# AC_MOVE-V3_4.net
KiCad netlist of a schematic drawn in Altium Designer
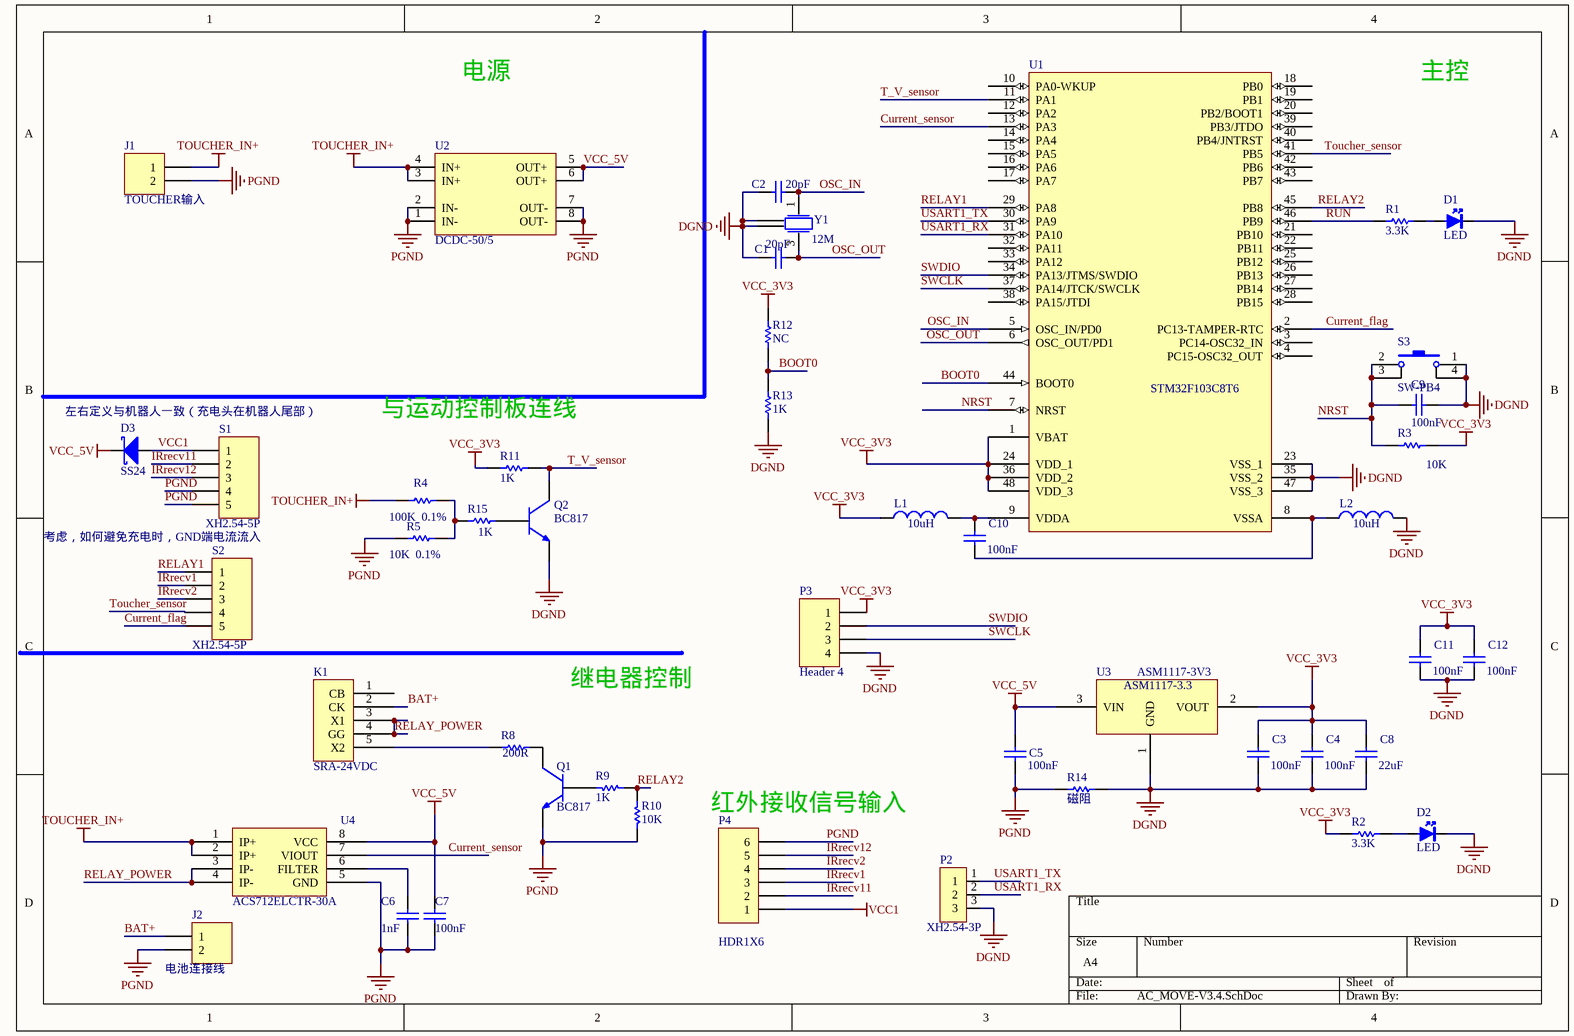
[diagram p0: AC_MOVE-V3.4.SchDoc]

(export (version "E")
  (design (tool "Eeschema 10.0.6"))
  (components
    (comp (ref "C1")
      (value "20pF")
      (footprint "C0805")
      (description "Capacitor")
      (fields (field (name "PUBLISHER") "Altium Limited"))
      (libsource (lib "Miscellaneous Devices") (part "Cap"))
    )
    (comp (ref "C2")
      (value "20pF")
      (footprint "C0805")
      (description "Capacitor")
      (fields (field (name "PUBLISHER") "Altium Limited"))
      (libsource (lib "Miscellaneous Devices") (part "Cap"))
    )
    (comp (ref "C3")
      (value "100nF")
      (footprint "boocax_schlib:C0805")
      (description "Capacitor")
      (fields (field (name "Comment") "Cap") (field (name "PUBLISHER") "Altium Limited"))
      (libsource (lib "boocax_schlib") (part "Cap"))
    )
    (comp (ref "C4")
      (value "100nF")
      (footprint "boocax_schlib:C0805")
      (description "Capacitor")
      (fields (field (name "Comment") "Cap") (field (name "PUBLISHER") "Altium Limited"))
      (libsource (lib "boocax_schlib") (part "Cap"))
    )
    (comp (ref "C5")
      (value "100nF")
      (footprint "boocax_schlib:C0805")
      (description "Capacitor")
      (fields (field (name "Comment") "Cap") (field (name "PUBLISHER") "Altium Limited"))
      (libsource (lib "boocax_schlib") (part "Cap"))
    )
    (comp (ref "C6")
      (value "1nF")
      (footprint "boocax_schlib:C0805")
      (description "Capacitor")
      (fields (field (name "Comment") "Cap") (field (name "PUBLISHER") "Altium Limited"))
      (libsource (lib "boocax_schlib") (part "Cap"))
    )
    (comp (ref "C7")
      (value "100nF")
      (footprint "boocax_schlib:C0805")
      (description "Capacitor")
      (fields (field (name "Comment") "Cap") (field (name "PUBLISHER") "Altium Limited"))
      (libsource (lib "boocax_schlib") (part "Cap"))
    )
    (comp (ref "C8")
      (value "22uF")
      (footprint "boocax_schlib:C0805")
      (description "Capacitor")
      (fields (field (name "Comment") "Cap") (field (name "PUBLISHER") "Altium Limited"))
      (libsource (lib "boocax_schlib") (part "Cap"))
    )
    (comp (ref "C9")
      (value "100nF")
      (footprint "C0805")
      (description "Capacitor")
      (fields (field (name "Comment") "Cap") (field (name "PUBLISHER") "Altium Limited"))
      (libsource (lib "boocax_schlib") (part "Cap"))
    )
    (comp (ref "C10")
      (value "100nF")
      (footprint "C0805")
      (description "Capacitor")
      (fields (field (name "Comment") "Cap") (field (name "PUBLISHER") "Altium Limited"))
      (libsource (lib "boocax_schlib") (part "Cap"))
    )
    (comp (ref "C11")
      (value "100nF")
      (footprint "C0805")
      (description "Capacitor")
      (fields (field (name "Comment") "Cap") (field (name "PUBLISHER") "Altium Limited"))
      (libsource (lib "boocax_schlib") (part "Cap"))
    )
    (comp (ref "C12")
      (value "100nF")
      (footprint "C0805")
      (description "Capacitor")
      (fields (field (name "Comment") "Cap") (field (name "PUBLISHER") "Altium Limited"))
      (libsource (lib "boocax_schlib") (part "Cap"))
    )
    (comp (ref "D1")
      (value "LED")
      (footprint "LED0805")
      (libsource (lib "boocax_schlib-20171017-1-dkw") (part "LED"))
    )
    (comp (ref "D2")
      (value "LED")
      (footprint "LED0805")
      (libsource (lib "boocax_schlib-20171017-1-dkw") (part "LED"))
    )
    (comp (ref "D3")
      (value "SS24")
      (footprint "D-SMA")
      (description "肖特基二极管")
      (fields (field (name "Comment") "Diode-Schottky") (field (name "PUBLISHER") "Altium Limited"))
      (libsource (lib "boocax_schlib-20171017-1-dkw") (part "Diode-Schottky"))
    )
    (comp (ref "J1")
      (value "TOUCHER输入")
      (footprint "6-0805_M")
      (description "Header, 2-Pin")
      (fields (field (name "PUBLISHER") "Altium Limited"))
      (libsource (lib "Miscellaneous Connectors") (part "Header 2"))
    )
    (comp (ref "J2")
      (value "电池连接线")
      (footprint "DIODE-AXL")
      (description "Header, 2-Pin")
      (fields (field (name "PUBLISHER") "Altium Limited"))
      (libsource (lib "") (part "Header 2_1"))
    )
    (comp (ref "K1")
      (value "SRA-24VDC")
      (footprint "SRD-05VDC")
      (libsource (lib "Schlib1") (part "SRD-05VDC"))
    )
    (comp (ref "L1")
      (value "10uH")
      (footprint "R0805")
      (description "Inductor")
      (fields (field (name "PUBLISHER") "Altium Limited"))
      (libsource (lib "Miscellaneous Devices") (part "Inductor"))
    )
    (comp (ref "L2")
      (value "10uH")
      (footprint "R0805")
      (description "Inductor")
      (fields (field (name "PUBLISHER") "Altium Limited"))
      (libsource (lib "Miscellaneous Devices") (part "Inductor"))
    )
    (comp (ref "P2")
      (value "XH2.54-3P")
      (footprint "boocax_schlib:XH2.54-3P")
      (fields (field (name "Comment") "MCU"))
      (libsource (lib "boocax_schlib") (part "Conn_1*3"))
    )
    (comp (ref "P3")
      (value "Header 4")
      (footprint "HDR1X4")
      (description "Header, 4-Pin")
      (fields (field (name "PUBLISHER") "Altium Limited"))
      (libsource (lib "Miscellaneous Connectors") (part "Header 4"))
    )
    (comp (ref "P4")
      (value "HDR1X6")
      (footprint "HDR1X6")
      (description "Header, 6-Pin")
      (fields (field (name "Comment") "Header 6") (field (name "PUBLISHER") "Altium Limited"))
      (libsource (lib "Miscellaneous Connectors") (part "Header 6"))
    )
    (comp (ref "Q1")
      (value "BC817")
      (footprint "SOT-23_N")
      (description "NPN 45V 功耗 310mW")
      (libsource (lib "Schlib1") (part "mNPN"))
    )
    (comp (ref "Q2")
      (value "BC817")
      (footprint "SOT-23_N")
      (description "NPN 45V 功耗 310mW")
      (libsource (lib "Schlib1") (part "mNPN"))
    )
    (comp (ref "R1")
      (value "3.3K")
      (footprint "R0805")
      (description "Resistor")
      (fields (field (name "Comment") "Res1") (field (name "PUBLISHER") "Altium Limited"))
      (libsource (lib "boocax_schlib-20171017-1-dkw") (part "Res1"))
    )
    (comp (ref "R2")
      (value "3.3K")
      (footprint "R0805")
      (description "Resistor")
      (fields (field (name "Comment") "Res1") (field (name "PUBLISHER") "Altium Limited"))
      (libsource (lib "boocax_schlib-20171017-1-dkw") (part "Res1"))
    )
    (comp (ref "R3")
      (value "10K")
      (footprint "R0805")
      (description "Resistor")
      (fields (field (name "Comment") "Res1") (field (name "PUBLISHER") "Altium Limited"))
      (libsource (lib "boocax_schlib-20171017-1-dkw") (part "Res1"))
    )
    (comp (ref "R4")
      (value "100K  0.1%")
      (footprint "R0805")
      (description "Resistor")
      (fields (field (name "Comment") "Res1") (field (name "PUBLISHER") "Altium Limited"))
      (libsource (lib "boocax_schlib-20171017-1-dkw") (part "Res1"))
    )
    (comp (ref "R5")
      (value "10K  0.1%")
      (footprint "R0805")
      (description "Resistor")
      (fields (field (name "Comment") "Res1") (field (name "PUBLISHER") "Altium Limited"))
      (libsource (lib "boocax_schlib-20171017-1-dkw") (part "Res1"))
    )
    (comp (ref "R8")
      (value "200R")
      (footprint "2512")
      (description "Resistor")
      (fields (field (name "Comment") "Res1") (field (name "PUBLISHER") "Altium Limited"))
      (libsource (lib "Miscellaneous Devices") (part "Res1"))
    )
    (comp (ref "R9")
      (value "1K")
      (footprint "R0805")
      (description "Resistor")
      (fields (field (name "Comment") "Res1") (field (name "PUBLISHER") "Altium Limited"))
      (libsource (lib "boocax_schlib-20171017-1-dkw") (part "Res1"))
    )
    (comp (ref "R10")
      (value "10K")
      (footprint "R0805")
      (description "Resistor")
      (fields (field (name "Comment") "Res1") (field (name "PUBLISHER") "Altium Limited"))
      (libsource (lib "") (part "Res1_1"))
    )
    (comp (ref "R11")
      (value "1K")
      (footprint "R0805")
      (description "Resistor")
      (fields (field (name "Comment") "Res1") (field (name "PUBLISHER") "Altium Limited"))
      (libsource (lib "boocax_schlib-20171017-1-dkw") (part "Res1"))
    )
    (comp (ref "R12")
      (value "NC")
      (footprint "0805-1")
      (description "Resistor")
      (fields (field (name "Comment") "Res1") (field (name "PUBLISHER") "Altium Limited"))
      (libsource (lib "boocax_schlib-20171017-1-dkw") (part "Res1"))
    )
    (comp (ref "R13")
      (value "1K")
      (footprint "R0805")
      (description "Resistor")
      (fields (field (name "Comment") "Res1") (field (name "PUBLISHER") "Altium Limited"))
      (libsource (lib "boocax_schlib-20171017-1-dkw") (part "Res1"))
    )
    (comp (ref "R14")
      (value "磁阻")
      (footprint "0805-1")
      (description "Resistor")
      (fields (field (name "Comment") "Res1") (field (name "PUBLISHER") "Altium Limited"))
      (libsource (lib "boocax_schlib-20171017-1-dkw") (part "Res1"))
    )
    (comp (ref "R15")
      (value "1K")
      (footprint "R0805")
      (description "Resistor")
      (fields (field (name "Comment") "Res1") (field (name "PUBLISHER") "Altium Limited"))
      (libsource (lib "boocax_schlib-20171017-1-dkw") (part "Res1"))
    )
    (comp (ref "S1")
      (value "XH2.54-5P")
      (footprint "XH2.54-5P")
      (description "Header, 5-Pin")
      (fields (field (name "Comment") "Header 5") (field (name "PUBLISHER") "Altium Limited"))
      (libsource (lib "Miscellaneous Connectors") (part "Header 5"))
    )
    (comp (ref "S2")
      (value "XH2.54-5P")
      (footprint "XH2.54-5P")
      (description "Header, 5-Pin")
      (fields (field (name "Comment") "Header 5") (field (name "PUBLISHER") "Altium Limited"))
      (libsource (lib "Miscellaneous Connectors") (part "Header 5"))
    )
    (comp (ref "S3")
      (value "SW-PB4")
      (footprint "RESET-SMD-1O4")
      (description "微动开关")
      (fields (field (name "PUBLISHER") "Altium Limited"))
      (libsource (lib "boocax_schlib") (part "SW-PB4"))
    )
    (comp (ref "U1")
      (value "STM32F103C8T6")
      (footprint "LQFP48_N")
      (description "STM32 ARM-based 32-bit MCU with 64 Kbytes Flash, 48-pin LQFP, Industrial Temperature")
      (fields (field (name "PUBLISHER") "Altium Limited"))
      (libsource (lib "ST Microcontroller 32-Bit STM32") (part "STM32F103C8T6"))
    )
    (comp (ref "U2")
      (value "DCDC-50/5")
      (footprint "boocax_schlib:DCDC50/5")
      (libsource (lib "boocax_schlib") (part "DCDC-50/5"))
    )
    (comp (ref "U3")
      (value "ASM1117-3V3")
      (footprint "boocax_schlib:ASM1117-3V3")
      (libsource (lib "boocax_schlib") (part "ASM1117-3V3"))
    )
    (comp (ref "U4")
      (value "ACS712ELCTR-30A")
      (footprint "ACS712-SOIC8")
      (libsource (lib "boocax_schlib") (part "ACS712"))
    )
    (comp (ref "Y1")
      (value "12M")
      (footprint "EPSON-16M")
      (fields (field (name "Comment") "XTAL-4PIN"))
      (libsource (lib "fszhang") (part "XTAL-4PIN"))
    )
  )
  (nets
    (net (code "1") (name "/BAT+") (class "Default")
      (node (ref "J2") (pin "1") (pinfunction "1_1") (pintype "passive"))
      (node (ref "K1") (pin "2") (pinfunction "CK_2") (pintype "passive"))
    )
    (net (code "2") (name "/BOOT0") (class "Default")
      (node (ref "R12") (pin "1") (pinfunction "1_1") (pintype "passive"))
      (node (ref "R13") (pin "1") (pinfunction "1_1") (pintype "passive"))
      (node (ref "U1") (pin "44") (pinfunction "BOOT0_44") (pintype "input"))
    )
    (net (code "3") (name "/Current_flag") (class "Default")
      (node (ref "S2") (pin "5") (pinfunction "5_5") (pintype "passive"))
      (node (ref "U1") (pin "2") (pinfunction "PC13-TAMPER-RTC_2") (pintype "bidirectional"))
    )
    (net (code "4") (name "/Current_sensor") (class "Default")
      (node (ref "U1") (pin "13") (pinfunction "PA3_13") (pintype "bidirectional"))
      (node (ref "U4") (pin "7") (pinfunction "VIOUT_7") (pintype "passive"))
    )
    (net (code "5") (name "/IRrecv1") (class "Default")
      (node (ref "P4") (pin "3") (pinfunction "3_3") (pintype "passive"))
      (node (ref "S2") (pin "2") (pinfunction "2_2") (pintype "passive"))
    )
    (net (code "6") (name "/IRrecv2") (class "Default")
      (node (ref "P4") (pin "4") (pinfunction "4_4") (pintype "passive"))
      (node (ref "S2") (pin "3") (pinfunction "3_3") (pintype "passive"))
    )
    (net (code "7") (name "/IRrecv11") (class "Default")
      (node (ref "P4") (pin "2") (pinfunction "2_2") (pintype "passive"))
      (node (ref "S1") (pin "2") (pinfunction "2_2") (pintype "passive"))
    )
    (net (code "8") (name "/IRrecv12") (class "Default")
      (node (ref "P4") (pin "5") (pinfunction "5_5") (pintype "passive"))
      (node (ref "S1") (pin "3") (pinfunction "3_3") (pintype "passive"))
    )
    (net (code "9") (name "/NRST") (class "Default")
      (node (ref "C9") (pin "1") (pinfunction "1_1") (pintype "passive"))
      (node (ref "R3") (pin "1") (pinfunction "1_1") (pintype "passive"))
      (node (ref "S3") (pin "2") (pinfunction "2_2") (pintype "passive"))
      (node (ref "S3") (pin "3") (pinfunction "3_3") (pintype "passive"))
      (node (ref "U1") (pin "7") (pinfunction "NRST_7") (pintype "bidirectional"))
    )
    (net (code "10") (name "/OSC_IN") (class "Default")
      (node (ref "C2") (pin "1") (pinfunction "1_1") (pintype "passive"))
      (node (ref "U1") (pin "5") (pinfunction "OSC_IN/PD0_5") (pintype "input"))
      (node (ref "Y1") (pin "1") (pinfunction "1_1") (pintype "passive"))
    )
    (net (code "11") (name "/OSC_OUT") (class "Default")
      (node (ref "C1") (pin "1") (pinfunction "1_1") (pintype "passive"))
      (node (ref "U1") (pin "6") (pinfunction "OSC_OUT/PD1_6") (pintype "output"))
      (node (ref "Y1") (pin "3") (pinfunction "3_3") (pintype "passive"))
    )
    (net (code "12") (name "/RELAY1") (class "Default")
      (node (ref "S2") (pin "1") (pinfunction "1_1") (pintype "passive"))
      (node (ref "U1") (pin "29") (pinfunction "PA8_29") (pintype "bidirectional"))
    )
    (net (code "13") (name "/RELAY2") (class "Default")
      (node (ref "R10") (pin "2") (pinfunction "2_2") (pintype "passive"))
      (node (ref "R9") (pin "2") (pinfunction "2_2") (pintype "passive"))
      (node (ref "U1") (pin "45") (pinfunction "PB8_45") (pintype "bidirectional"))
    )
    (net (code "14") (name "/RELAY_POWER") (class "Default")
      (node (ref "K1") (pin "3") (pinfunction "X1_3") (pintype "passive"))
      (node (ref "K1") (pin "4") (pinfunction "GG_4") (pintype "passive"))
      (node (ref "U4") (pin "3") (pinfunction "IP-_3") (pintype "passive"))
      (node (ref "U4") (pin "4") (pinfunction "IP-_4") (pintype "passive"))
    )
    (net (code "15") (name "/RUN") (class "Default")
      (node (ref "R1") (pin "2") (pinfunction "2_2") (pintype "passive"))
      (node (ref "U1") (pin "46") (pinfunction "PB9_46") (pintype "bidirectional"))
    )
    (net (code "16") (name "/SWCLK") (class "Default")
      (node (ref "P3") (pin "3") (pinfunction "3_3") (pintype "passive"))
      (node (ref "U1") (pin "37") (pinfunction "PA14/JTCK/SWCLK_37") (pintype "bidirectional"))
    )
    (net (code "17") (name "/SWDIO") (class "Default")
      (node (ref "P3") (pin "2") (pinfunction "2_2") (pintype "passive"))
      (node (ref "U1") (pin "34") (pinfunction "PA13/JTMS/SWDIO_34") (pintype "bidirectional"))
    )
    (net (code "18") (name "/T_V_sensor") (class "Default")
      (node (ref "Q2") (pin "3") (pinfunction "C_3") (pintype "passive"))
      (node (ref "R11") (pin "2") (pinfunction "2_2") (pintype "passive"))
      (node (ref "U1") (pin "11") (pinfunction "PA1_11") (pintype "bidirectional"))
    )
    (net (code "19") (name "/Toucher_sensor") (class "Default")
      (node (ref "S2") (pin "4") (pinfunction "4_4") (pintype "passive"))
      (node (ref "U1") (pin "41") (pinfunction "PB5_41") (pintype "bidirectional"))
    )
    (net (code "20") (name "/USART1_RX") (class "Default")
      (node (ref "P2") (pin "2") (pinfunction "2_2") (pintype "passive"))
      (node (ref "U1") (pin "31") (pinfunction "PA10_31") (pintype "bidirectional"))
    )
    (net (code "21") (name "/USART1_TX") (class "Default")
      (node (ref "P2") (pin "1") (pinfunction "1_1") (pintype "passive"))
      (node (ref "U1") (pin "30") (pinfunction "PA9_30") (pintype "bidirectional"))
    )
    (net (code "22") (name "DGND") (class "Default")
      (node (ref "C1") (pin "2") (pinfunction "2_2") (pintype "passive"))
      (node (ref "C11") (pin "1") (pinfunction "1_1") (pintype "passive"))
      (node (ref "C12") (pin "1") (pinfunction "1_1") (pintype "passive"))
      (node (ref "C2") (pin "2") (pinfunction "2_2") (pintype "passive"))
      (node (ref "C3") (pin "1") (pinfunction "1_1") (pintype "passive"))
      (node (ref "C4") (pin "1") (pinfunction "1_1") (pintype "passive"))
      (node (ref "C8") (pin "1") (pinfunction "1_1") (pintype "passive"))
      (node (ref "C9") (pin "2") (pinfunction "2_2") (pintype "passive"))
      (node (ref "D1") (pin "2") (pinfunction "K_2") (pintype "passive"))
      (node (ref "D2") (pin "2") (pinfunction "K_2") (pintype "passive"))
      (node (ref "L2") (pin "2") (pinfunction "2_2") (pintype "passive"))
      (node (ref "P2") (pin "3") (pinfunction "3_3") (pintype "passive"))
      (node (ref "P3") (pin "4") (pinfunction "4_4") (pintype "passive"))
      (node (ref "Q2") (pin "2") (pinfunction "E_2") (pintype "passive"))
      (node (ref "R13") (pin "2") (pinfunction "2_2") (pintype "passive"))
      (node (ref "R14") (pin "1") (pinfunction "1_1") (pintype "passive"))
      (node (ref "S3") (pin "1") (pinfunction "1_1") (pintype "passive"))
      (node (ref "S3") (pin "4") (pinfunction "4_4") (pintype "passive"))
      (node (ref "U1") (pin "23") (pinfunction "VSS_1_23") (pintype "power_in"))
      (node (ref "U1") (pin "35") (pinfunction "VSS_2_35") (pintype "power_in"))
      (node (ref "U1") (pin "47") (pinfunction "VSS_3_47") (pintype "power_in"))
      (node (ref "U3") (pin "1") (pinfunction "GND_1") (pintype "passive"))
      (node (ref "Y1") (pin "2") (pinfunction "2_2") (pintype "passive"))
      (node (ref "Y1") (pin "4") (pinfunction "4_4") (pintype "passive"))
    )
    (net (code "23") (name "Net-(D1-A)") (class "Default")
      (node (ref "D1") (pin "1") (pinfunction "A_1") (pintype "passive"))
      (node (ref "R1") (pin "1") (pinfunction "1_1") (pintype "passive"))
    )
    (net (code "24") (name "Net-(D2-A)") (class "Default")
      (node (ref "D2") (pin "1") (pinfunction "A_1") (pintype "passive"))
      (node (ref "R2") (pin "1") (pinfunction "1_1") (pintype "passive"))
    )
    (net (code "25") (name "Net-(K1-X2)") (class "Default")
      (node (ref "K1") (pin "5") (pinfunction "X2_5") (pintype "passive"))
      (node (ref "R8") (pin "2") (pinfunction "2_2") (pintype "passive"))
    )
    (net (code "26") (name "Net-(Q1-B)") (class "Default")
      (node (ref "Q1") (pin "1") (pinfunction "B_1") (pintype "passive"))
      (node (ref "R9") (pin "1") (pinfunction "1_1") (pintype "passive"))
    )
    (net (code "27") (name "Net-(Q1-C)") (class "Default")
      (node (ref "Q1") (pin "3") (pinfunction "C_3") (pintype "passive"))
      (node (ref "R8") (pin "1") (pinfunction "1_1") (pintype "passive"))
    )
    (net (code "28") (name "Net-(Q2-B)") (class "Default")
      (node (ref "Q2") (pin "1") (pinfunction "B_1") (pintype "passive"))
      (node (ref "R15") (pin "2") (pinfunction "2_2") (pintype "passive"))
    )
    (net (code "29") (name "Net-(R15-Pad1)") (class "Default")
      (node (ref "R15") (pin "1") (pinfunction "1_1") (pintype "passive"))
      (node (ref "R4") (pin "2") (pinfunction "2_2") (pintype "passive"))
      (node (ref "R5") (pin "2") (pinfunction "2_2") (pintype "passive"))
    )
    (net (code "30") (name "Net-(U1-VDDA)") (class "Default")
      (node (ref "C10") (pin "2") (pinfunction "2_2") (pintype "passive"))
      (node (ref "L1") (pin "2") (pinfunction "2_2") (pintype "passive"))
      (node (ref "U1") (pin "9") (pinfunction "VDDA_9") (pintype "power_in"))
    )
    (net (code "31") (name "Net-(U1-VSSA)") (class "Default")
      (node (ref "C10") (pin "1") (pinfunction "1_1") (pintype "passive"))
      (node (ref "L2") (pin "1") (pinfunction "1_1") (pintype "passive"))
      (node (ref "U1") (pin "8") (pinfunction "VSSA_8") (pintype "power_in"))
    )
    (net (code "32") (name "Net-(U4-FILTER)") (class "Default")
      (node (ref "C6") (pin "2") (pinfunction "2_2") (pintype "passive"))
      (node (ref "U4") (pin "6") (pinfunction "FILTER_6") (pintype "passive"))
    )
    (net (code "33") (name "PGND") (class "Default")
      (node (ref "C5") (pin "1") (pinfunction "1_1") (pintype "passive"))
      (node (ref "C6") (pin "1") (pinfunction "1_1") (pintype "passive"))
      (node (ref "C7") (pin "1") (pinfunction "1_1") (pintype "passive"))
      (node (ref "J1") (pin "2") (pinfunction "2_2") (pintype "passive"))
      (node (ref "J2") (pin "2") (pinfunction "2_2") (pintype "passive"))
      (node (ref "P4") (pin "6") (pinfunction "6_6") (pintype "passive"))
      (node (ref "Q1") (pin "2") (pinfunction "E_2") (pintype "passive"))
      (node (ref "R10") (pin "1") (pinfunction "1_1") (pintype "passive"))
      (node (ref "R14") (pin "2") (pinfunction "2_2") (pintype "passive"))
      (node (ref "R5") (pin "1") (pinfunction "1_1") (pintype "passive"))
      (node (ref "S1") (pin "4") (pinfunction "4_4") (pintype "passive"))
      (node (ref "S1") (pin "5") (pinfunction "5_5") (pintype "passive"))
      (node (ref "U2") (pin "1") (pinfunction "IN-_1") (pintype "passive"))
      (node (ref "U2") (pin "2") (pinfunction "IN-_2") (pintype "passive"))
      (node (ref "U2") (pin "7") (pinfunction "OUT-_7") (pintype "passive"))
      (node (ref "U2") (pin "8") (pinfunction "OUT-_8") (pintype "passive"))
      (node (ref "U4") (pin "5") (pinfunction "GND_5") (pintype "passive"))
    )
    (net (code "34") (name "TOUCHER_IN+") (class "Default")
      (node (ref "J1") (pin "1") (pinfunction "1_1") (pintype "passive"))
      (node (ref "R4") (pin "1") (pinfunction "1_1") (pintype "passive"))
      (node (ref "U2") (pin "3") (pinfunction "IN+_3") (pintype "passive"))
      (node (ref "U2") (pin "4") (pinfunction "IN+_4") (pintype "passive"))
      (node (ref "U4") (pin "1") (pinfunction "IP+_1") (pintype "passive"))
      (node (ref "U4") (pin "2") (pinfunction "IP+_2") (pintype "passive"))
    )
    (net (code "35") (name "VCC1") (class "Default")
      (node (ref "D3") (pin "1") (pinfunction "A_1") (pintype "passive"))
      (node (ref "P4") (pin "1") (pinfunction "1_1") (pintype "passive"))
      (node (ref "S1") (pin "1") (pinfunction "1_1") (pintype "passive"))
    )
    (net (code "36") (name "VCC_3V3") (class "Default")
      (node (ref "C11") (pin "2") (pinfunction "2_2") (pintype "passive"))
      (node (ref "C12") (pin "2") (pinfunction "2_2") (pintype "passive"))
      (node (ref "C3") (pin "2") (pinfunction "2_2") (pintype "passive"))
      (node (ref "C4") (pin "2") (pinfunction "2_2") (pintype "passive"))
      (node (ref "C8") (pin "2") (pinfunction "2_2") (pintype "passive"))
      (node (ref "L1") (pin "1") (pinfunction "1_1") (pintype "passive"))
      (node (ref "P3") (pin "1") (pinfunction "1_1") (pintype "passive"))
      (node (ref "R11") (pin "1") (pinfunction "1_1") (pintype "passive"))
      (node (ref "R12") (pin "2") (pinfunction "2_2") (pintype "passive"))
      (node (ref "R2") (pin "2") (pinfunction "2_2") (pintype "passive"))
      (node (ref "R3") (pin "2") (pinfunction "2_2") (pintype "passive"))
      (node (ref "U1") (pin "1") (pinfunction "VBAT_1") (pintype "power_in"))
      (node (ref "U1") (pin "24") (pinfunction "VDD_1_24") (pintype "power_in"))
      (node (ref "U1") (pin "36") (pinfunction "VDD_2_36") (pintype "power_in"))
      (node (ref "U1") (pin "48") (pinfunction "VDD_3_48") (pintype "power_in"))
      (node (ref "U3") (pin "2") (pinfunction "VOUT_2") (pintype "passive"))
    )
    (net (code "37") (name "VCC_5V") (class "Default")
      (node (ref "C5") (pin "2") (pinfunction "2_2") (pintype "passive"))
      (node (ref "C7") (pin "2") (pinfunction "2_2") (pintype "passive"))
      (node (ref "D3") (pin "2") (pinfunction "K_2") (pintype "passive"))
      (node (ref "U2") (pin "5") (pinfunction "OUT+_5") (pintype "passive"))
      (node (ref "U2") (pin "6") (pinfunction "OUT+_6") (pintype "passive"))
      (node (ref "U3") (pin "3") (pinfunction "VIN_3") (pintype "passive"))
      (node (ref "U4") (pin "8") (pinfunction "VCC_8") (pintype "passive"))
    )
    (net (code "38") (name "unconnected-(K1-CB-Pad1)") (class "Default")
      (node (ref "K1") (pin "1") (pinfunction "CB_1") (pintype "passive"))
    )
    (net (code "39") (name "unconnected-(U1-PA0-WKUP-Pad10)") (class "Default")
      (node (ref "U1") (pin "10") (pinfunction "PA0-WKUP_10") (pintype "bidirectional"))
    )
    (net (code "40") (name "unconnected-(U1-PA2-Pad12)") (class "Default")
      (node (ref "U1") (pin "12") (pinfunction "PA2_12") (pintype "bidirectional"))
    )
    (net (code "41") (name "unconnected-(U1-PA4-Pad14)") (class "Default")
      (node (ref "U1") (pin "14") (pinfunction "PA4_14") (pintype "bidirectional"))
    )
    (net (code "42") (name "unconnected-(U1-PA5-Pad15)") (class "Default")
      (node (ref "U1") (pin "15") (pinfunction "PA5_15") (pintype "bidirectional"))
    )
    (net (code "43") (name "unconnected-(U1-PA6-Pad16)") (class "Default")
      (node (ref "U1") (pin "16") (pinfunction "PA6_16") (pintype "bidirectional"))
    )
    (net (code "44") (name "unconnected-(U1-PA7-Pad17)") (class "Default")
      (node (ref "U1") (pin "17") (pinfunction "PA7_17") (pintype "bidirectional"))
    )
    (net (code "45") (name "unconnected-(U1-PA11-Pad32)") (class "Default")
      (node (ref "U1") (pin "32") (pinfunction "PA11_32") (pintype "bidirectional"))
    )
    (net (code "46") (name "unconnected-(U1-PA12-Pad33)") (class "Default")
      (node (ref "U1") (pin "33") (pinfunction "PA12_33") (pintype "bidirectional"))
    )
    (net (code "47") (name "unconnected-(U1-PA15{slash}JTDI-Pad38)") (class "Default")
      (node (ref "U1") (pin "38") (pinfunction "PA15/JTDI_38") (pintype "bidirectional"))
    )
    (net (code "48") (name "unconnected-(U1-PB0-Pad18)") (class "Default")
      (node (ref "U1") (pin "18") (pinfunction "PB0_18") (pintype "bidirectional"))
    )
    (net (code "49") (name "unconnected-(U1-PB1-Pad19)") (class "Default")
      (node (ref "U1") (pin "19") (pinfunction "PB1_19") (pintype "bidirectional"))
    )
    (net (code "50") (name "unconnected-(U1-PB2{slash}BOOT1-Pad20)") (class "Default")
      (node (ref "U1") (pin "20") (pinfunction "PB2/BOOT1_20") (pintype "bidirectional"))
    )
    (net (code "51") (name "unconnected-(U1-PB3{slash}JTDO-Pad39)") (class "Default")
      (node (ref "U1") (pin "39") (pinfunction "PB3/JTDO_39") (pintype "bidirectional"))
    )
    (net (code "52") (name "unconnected-(U1-PB4{slash}JNTRST-Pad40)") (class "Default")
      (node (ref "U1") (pin "40") (pinfunction "PB4/JNTRST_40") (pintype "bidirectional"))
    )
    (net (code "53") (name "unconnected-(U1-PB6-Pad42)") (class "Default")
      (node (ref "U1") (pin "42") (pinfunction "PB6_42") (pintype "bidirectional"))
    )
    (net (code "54") (name "unconnected-(U1-PB7-Pad43)") (class "Default")
      (node (ref "U1") (pin "43") (pinfunction "PB7_43") (pintype "bidirectional"))
    )
    (net (code "55") (name "unconnected-(U1-PB10-Pad21)") (class "Default")
      (node (ref "U1") (pin "21") (pinfunction "PB10_21") (pintype "bidirectional"))
    )
    (net (code "56") (name "unconnected-(U1-PB11-Pad22)") (class "Default")
      (node (ref "U1") (pin "22") (pinfunction "PB11_22") (pintype "bidirectional"))
    )
    (net (code "57") (name "unconnected-(U1-PB12-Pad25)") (class "Default")
      (node (ref "U1") (pin "25") (pinfunction "PB12_25") (pintype "bidirectional"))
    )
    (net (code "58") (name "unconnected-(U1-PB13-Pad26)") (class "Default")
      (node (ref "U1") (pin "26") (pinfunction "PB13_26") (pintype "bidirectional"))
    )
    (net (code "59") (name "unconnected-(U1-PB14-Pad27)") (class "Default")
      (node (ref "U1") (pin "27") (pinfunction "PB14_27") (pintype "bidirectional"))
    )
    (net (code "60") (name "unconnected-(U1-PB15-Pad28)") (class "Default")
      (node (ref "U1") (pin "28") (pinfunction "PB15_28") (pintype "bidirectional"))
    )
    (net (code "61") (name "unconnected-(U1-PC14-OSC32_IN-Pad3)") (class "Default")
      (node (ref "U1") (pin "3") (pinfunction "PC14-OSC32_IN_3") (pintype "bidirectional"))
    )
    (net (code "62") (name "unconnected-(U1-PC15-OSC32_OUT-Pad4)") (class "Default")
      (node (ref "U1") (pin "4") (pinfunction "PC15-OSC32_OUT_4") (pintype "bidirectional"))
    )
  )
)
